# succh_punker.net
KiCad netlist of a schematic drawn in EAGLE
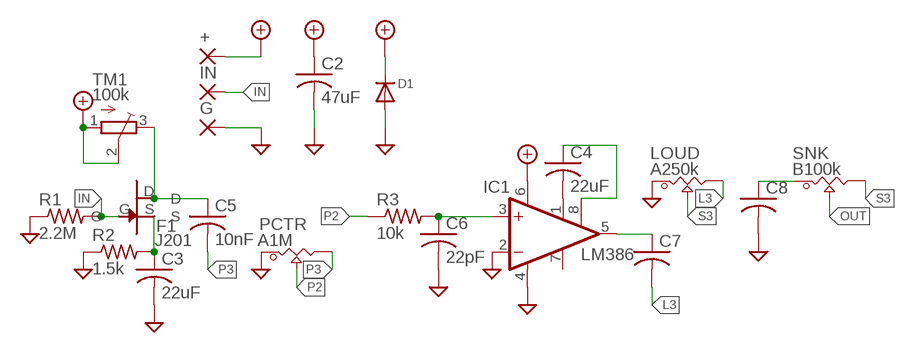
[diagram p0: schematic, sheet 1]

(export (version "E")
  (design (tool "Eeschema 10.0.6"))
  (components
    (comp (ref "+")
      (value "SMD2")
      (footprint "eagle-import:SMD1,27-2,54")
      (libsource (lib "eagle-import") (part "SMD2"))
    )
    (comp (ref "C2")
      (value "47uF")
      (footprint "eagle-import:C1210")
      (libsource (lib "eagle-import") (part "C-USC1210"))
    )
    (comp (ref "C3")
      (value "22uF")
      (footprint "eagle-import:C1210")
      (libsource (lib "eagle-import") (part "C-USC1210"))
    )
    (comp (ref "C4")
      (value "22uF")
      (footprint "eagle-import:C1210")
      (libsource (lib "eagle-import") (part "C-USC1210"))
    )
    (comp (ref "C5")
      (value "10nF")
      (footprint "eagle-import:C0603")
      (libsource (lib "eagle-import") (part "C-USC0603"))
    )
    (comp (ref "C6")
      (value "22pF")
      (footprint "eagle-import:C0603")
      (libsource (lib "eagle-import") (part "C-USC0603"))
    )
    (comp (ref "C7")
      (value "C-USC0603")
      (footprint "eagle-import:C0603")
      (libsource (lib "eagle-import") (part "C-USC0603"))
    )
    (comp (ref "C8")
      (value "C-USC0603")
      (footprint "eagle-import:C0603")
      (libsource (lib "eagle-import") (part "C-USC0603"))
    )
    (comp (ref "D1")
      (value "DIODESOD-123")
      (footprint "eagle-import:SOD-123")
      (libsource (lib "eagle-import") (part "DIODESOD-123"))
    )
    (comp (ref "F1")
      (value "J201")
      (footprint "eagle-import:MMBFJ201")
      (libsource (lib "eagle-import") (part "MMBFJ201"))
    )
    (comp (ref "G")
      (value "SMD2")
      (footprint "eagle-import:SMD1,27-2,54")
      (libsource (lib "eagle-import") (part "SMD2"))
    )
    (comp (ref "IC1")
      (value "LM386")
      (footprint "eagle-import:SO08")
      (libsource (lib "eagle-import") (part "LM386?-M1"))
    )
    (comp (ref "IN")
      (value "SMD2")
      (footprint "eagle-import:SMD1,27-2,54")
      (libsource (lib "eagle-import") (part "SMD2"))
    )
    (comp (ref "LOUD")
      (value "A250k")
      (footprint "eagle-import:POT_9MM_SMD")
      (libsource (lib "eagle-import") (part "POT_9MM_SMD"))
    )
    (comp (ref "PCTR")
      (value "A1M")
      (footprint "eagle-import:POT_9MM_SMD")
      (libsource (lib "eagle-import") (part "POT_9MM_SMD"))
    )
    (comp (ref "R1")
      (value "2.2M")
      (footprint "eagle-import:R0603")
      (libsource (lib "eagle-import") (part "R-US_R0603"))
    )
    (comp (ref "R2")
      (value "1.5k")
      (footprint "eagle-import:R0603")
      (libsource (lib "eagle-import") (part "R-US_R0603"))
    )
    (comp (ref "R3")
      (value "10k")
      (footprint "eagle-import:R0603")
      (libsource (lib "eagle-import") (part "R-US_R0603"))
    )
    (comp (ref "SNK")
      (value "B100k")
      (footprint "eagle-import:POT_9MM_SMD")
      (libsource (lib "eagle-import") (part "POT_9MM_SMD"))
    )
    (comp (ref "TM1")
      (value "100k")
      (footprint "eagle-import:TC33X")
      (libsource (lib "eagle-import") (part "TRIMPOTTC33X"))
    )
  )
  (nets
    (net (code "1") (name "+9V") (class "Default")
      (node (ref "+") (pin "1") (pinfunction "P_1") (pintype "passive"))
      (node (ref "C2") (pin "1") (pinfunction "1_1") (pintype "passive"))
      (node (ref "D1") (pin "C") (pinfunction "C_C") (pintype "passive"))
      (node (ref "IC1") (pin "6") (pinfunction "VS_6") (pintype "power_in"))
      (node (ref "TM1") (pin "1") (pinfunction "A_1") (pintype "passive"))
      (node (ref "TM1") (pin "2") (pinfunction "S_2") (pintype "passive"))
    )
    (net (code "2") (name "GND") (class "Default")
      (node (ref "C2") (pin "2") (pinfunction "2_2") (pintype "passive"))
      (node (ref "C3") (pin "2") (pinfunction "2_2") (pintype "passive"))
      (node (ref "C6") (pin "2") (pinfunction "2_2") (pintype "passive"))
      (node (ref "C8") (pin "2") (pinfunction "2_2") (pintype "passive"))
      (node (ref "D1") (pin "A") (pinfunction "A_A") (pintype "passive"))
      (node (ref "G") (pin "1") (pinfunction "P_1") (pintype "passive"))
      (node (ref "IC1") (pin "2") (pinfunction "-IN_2") (pintype "input"))
      (node (ref "IC1") (pin "4") (pinfunction "GND_4") (pintype "power_in"))
      (node (ref "LOUD") (pin "1") (pinfunction "1_1") (pintype "bidirectional"))
      (node (ref "PCTR") (pin "1") (pinfunction "1_1") (pintype "bidirectional"))
      (node (ref "R1") (pin "1") (pinfunction "1_1") (pintype "passive"))
      (node (ref "R2") (pin "1") (pinfunction "1_1") (pintype "passive"))
    )
    (net (code "3") (name "IN") (class "Default")
      (node (ref "F1") (pin "G") (pinfunction "G_G") (pintype "bidirectional"))
      (node (ref "IN") (pin "1") (pinfunction "P_1") (pintype "passive"))
      (node (ref "R1") (pin "2") (pinfunction "2_2") (pintype "passive"))
    )
    (net (code "4") (name "L3") (class "Default")
      (node (ref "C7") (pin "2") (pinfunction "2_2") (pintype "passive"))
      (node (ref "LOUD") (pin "3") (pinfunction "3_3") (pintype "bidirectional"))
    )
    (net (code "5") (name "Net-(C3-Pad1)") (class "Default")
      (node (ref "C3") (pin "1") (pinfunction "1_1") (pintype "passive"))
      (node (ref "F1") (pin "S") (pinfunction "S_S") (pintype "bidirectional"))
      (node (ref "R2") (pin "2") (pinfunction "2_2") (pintype "passive"))
    )
    (net (code "6") (name "Net-(C4-Pad1)") (class "Default")
      (node (ref "C4") (pin "1") (pinfunction "1_1") (pintype "passive"))
      (node (ref "IC1") (pin "8") (pinfunction "GAIN_8") (pintype "passive"))
    )
    (net (code "7") (name "Net-(C4-Pad2)") (class "Default")
      (node (ref "C4") (pin "2") (pinfunction "2_2") (pintype "passive"))
      (node (ref "IC1") (pin "1") (pinfunction "GAIN_1") (pintype "passive"))
    )
    (net (code "8") (name "Net-(C8-Pad1)") (class "Default")
      (node (ref "C8") (pin "1") (pinfunction "1_1") (pintype "passive"))
      (node (ref "SNK") (pin "1") (pinfunction "1_1") (pintype "bidirectional"))
    )
    (net (code "9") (name "Net-(IC1-+IN)") (class "Default")
      (node (ref "C6") (pin "1") (pinfunction "1_1") (pintype "passive"))
      (node (ref "IC1") (pin "3") (pinfunction "+IN_3") (pintype "input"))
      (node (ref "R3") (pin "2") (pinfunction "2_2") (pintype "passive"))
    )
    (net (code "10") (name "Net-(IC1-OUT)") (class "Default")
      (node (ref "C7") (pin "1") (pinfunction "1_1") (pintype "passive"))
      (node (ref "IC1") (pin "5") (pinfunction "OUT_5") (pintype "output"))
    )
    (net (code "11") (name "Net-(TM1-E)") (class "Default")
      (node (ref "C5") (pin "1") (pinfunction "1_1") (pintype "passive"))
      (node (ref "F1") (pin "D") (pinfunction "D_D") (pintype "bidirectional"))
      (node (ref "TM1") (pin "3") (pinfunction "E_3") (pintype "passive"))
    )
    (net (code "12") (name "OUT") (class "Default")
      (node (ref "SNK") (pin "2") (pinfunction "2_2") (pintype "bidirectional"))
    )
    (net (code "13") (name "P2") (class "Default")
      (node (ref "PCTR") (pin "2") (pinfunction "2_2") (pintype "bidirectional"))
      (node (ref "R3") (pin "1") (pinfunction "1_1") (pintype "passive"))
    )
    (net (code "14") (name "P3") (class "Default")
      (node (ref "C5") (pin "2") (pinfunction "2_2") (pintype "passive"))
      (node (ref "PCTR") (pin "3") (pinfunction "3_3") (pintype "bidirectional"))
    )
    (net (code "15") (name "S3") (class "Default")
      (node (ref "LOUD") (pin "2") (pinfunction "2_2") (pintype "bidirectional"))
      (node (ref "SNK") (pin "3") (pinfunction "3_3") (pintype "bidirectional"))
    )
    (net (code "16") (name "unconnected-(IC1-BYPASS-Pad7)") (class "Default")
      (node (ref "IC1") (pin "7") (pinfunction "BYPASS_7") (pintype "passive"))
    )
  )
)
